# Mach_dieu_khien_dong_co_dc.net
KiCad netlist of a schematic drawn in Altium Designer
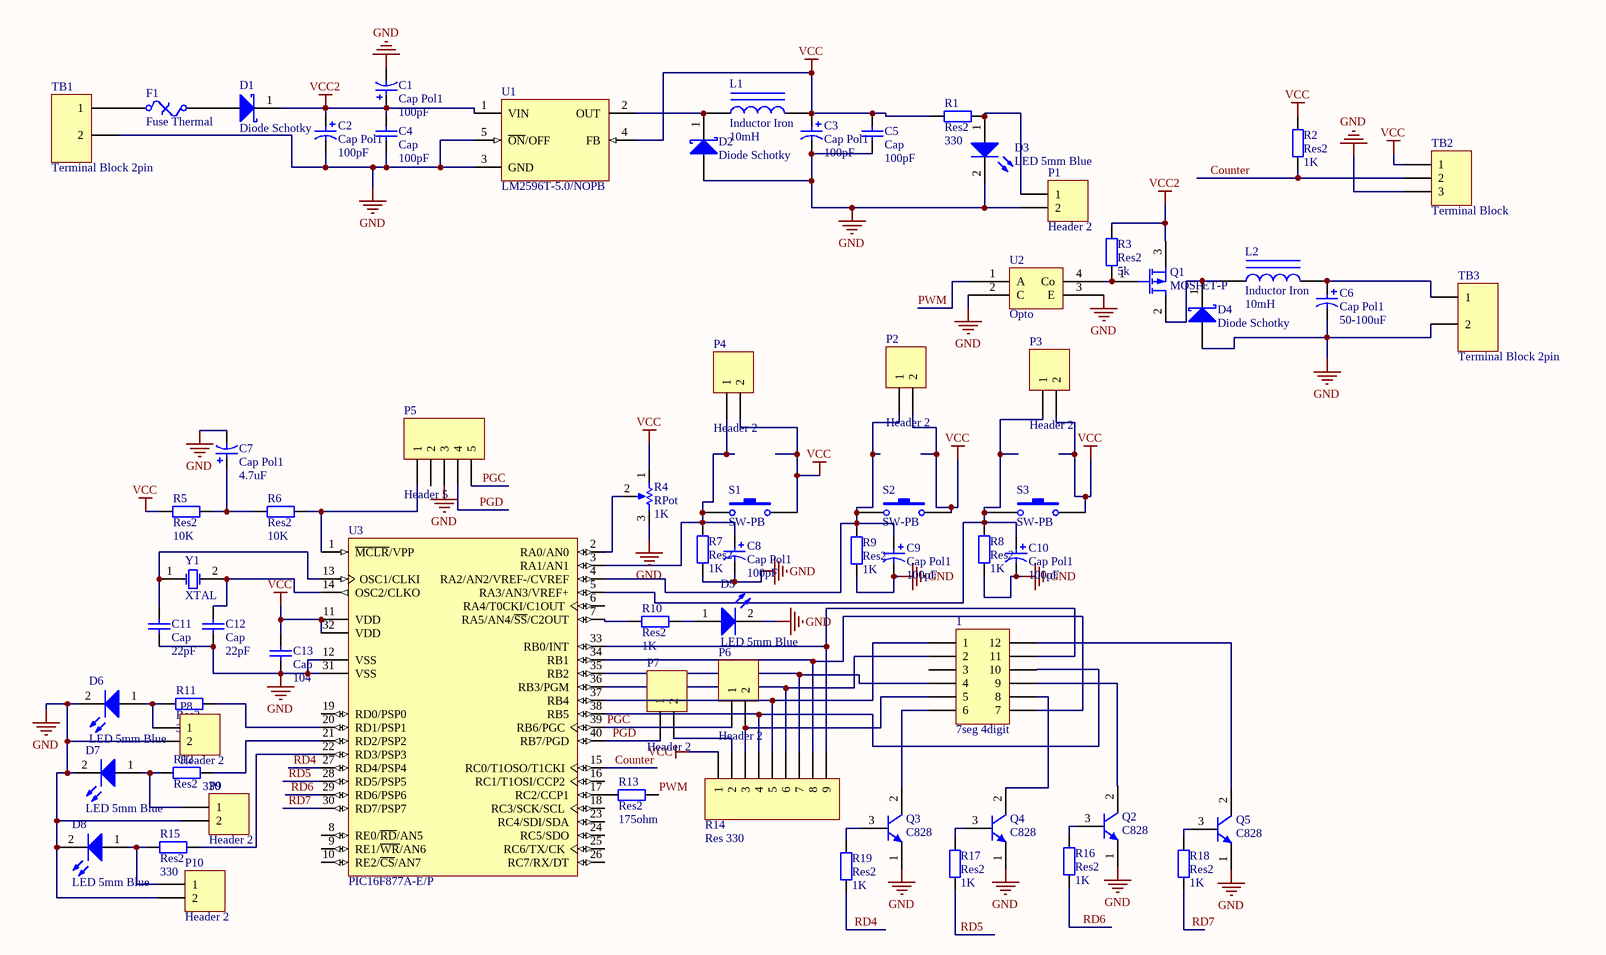
[diagram p0: Mach dieu khien dong co dc.SchDoc]

(export (version "E")
  (design (tool "Eeschema 10.0.6"))
  (components
    (comp (ref "1")
      (value "7seg 4digit")
      (footprint "LEDDIP-12/QUAD")
      (description "Header, 6-Pin, Dual row")
      (fields (field (name "PUBLISHER") "Altium Limited"))
      (libsource (lib "Manh") (part "7seg 4digit"))
    )
    (comp (ref "C1")
      (value "Cap Pol1")
      (footprint "Manh:CAPPR2-5x7")
      (description "Polarized Capacitor (Radial)")
      (fields (field (name "ALTIUM_VALUE") "100pF") (field (name "PUBLISHER") "Altium Limited"))
      (libsource (lib "Manh") (part "Cap Pol1"))
    )
    (comp (ref "C2")
      (value "Cap Pol1")
      (footprint "CAPPR2.5-6.3x5/H.9")
      (description "Polarized Capacitor (Radial)")
      (fields (field (name "ALTIUM_VALUE") "100pF") (field (name "PUBLISHER") "Altium Limited"))
      (libsource (lib "Manh") (part "Cap Pol1"))
    )
    (comp (ref "C3")
      (value "Cap Pol1")
      (footprint "CAPPR2.5-6.3x5/H.9")
      (description "Polarized Capacitor (Radial)")
      (fields (field (name "ALTIUM_VALUE") "100pF") (field (name "PUBLISHER") "Altium Limited"))
      (libsource (lib "Manh") (part "Cap Pol1"))
    )
    (comp (ref "C4")
      (value "Cap")
      (footprint "CAPNTO3.18-4.83x2.67")
      (description "Capacitor")
      (fields (field (name "ALTIUM_VALUE") "100pF") (field (name "PUBLISHER") "Altium Limited"))
      (libsource (lib "Manh") (part "Cap"))
    )
    (comp (ref "C5")
      (value "Cap")
      (footprint "CAPNTO3.18-4.83x2.67")
      (description "Capacitor")
      (fields (field (name "ALTIUM_VALUE") "100pF") (field (name "PUBLISHER") "Altium Limited"))
      (libsource (lib "Manh") (part "Cap"))
    )
    (comp (ref "C6")
      (value "Cap Pol1")
      (footprint "CAPPR2.5-6.3x5/H.9")
      (description "Polarized Capacitor (Radial)")
      (fields (field (name "ALTIUM_VALUE") "50-100uF") (field (name "PUBLISHER") "Altium Limited"))
      (libsource (lib "Manh") (part "Cap Pol1"))
    )
    (comp (ref "C7")
      (value "Cap Pol1")
      (footprint "CAPPR2-5x7")
      (description "Polarized Capacitor (Radial)")
      (fields (field (name "ALTIUM_VALUE") "4.7uF") (field (name "PUBLISHER") "Altium Limited"))
      (libsource (lib "Manh") (part "Cap Pol1"))
    )
    (comp (ref "C8")
      (value "Cap Pol1")
      (footprint "Manh:CAPPR2-5x7")
      (description "Polarized Capacitor (Radial)")
      (fields (field (name "ALTIUM_VALUE") "100pF") (field (name "PUBLISHER") "Altium Limited"))
      (libsource (lib "Manh") (part "Cap Pol1"))
    )
    (comp (ref "C9")
      (value "Cap Pol1")
      (footprint "Manh:CAPPR2-5x7")
      (description "Polarized Capacitor (Radial)")
      (fields (field (name "ALTIUM_VALUE") "100pF") (field (name "PUBLISHER") "Altium Limited"))
      (libsource (lib "Manh") (part "Cap Pol1"))
    )
    (comp (ref "C10")
      (value "Cap Pol1")
      (footprint "Manh:CAPPR2-5x7")
      (description "Polarized Capacitor (Radial)")
      (fields (field (name "ALTIUM_VALUE") "100pF") (field (name "PUBLISHER") "Altium Limited"))
      (libsource (lib "Manh") (part "Cap Pol1"))
    )
    (comp (ref "C11")
      (value "Cap")
      (footprint "CAPNTO3.18-4.83x2.67")
      (description "Capacitor")
      (fields (field (name "ALTIUM_VALUE") "22pF") (field (name "PUBLISHER") "Altium Limited"))
      (libsource (lib "Manh") (part "Cap"))
    )
    (comp (ref "C12")
      (value "Cap")
      (footprint "CAPNTO3.18-4.83x2.67")
      (description "Capacitor")
      (fields (field (name "ALTIUM_VALUE") "22pF") (field (name "PUBLISHER") "Altium Limited"))
      (libsource (lib "Manh") (part "Cap"))
    )
    (comp (ref "C13")
      (value "Cap")
      (footprint "CAPNTO3.18-4.83x2.67")
      (description "Capacitor")
      (fields (field (name "ALTIUM_VALUE") "104") (field (name "PUBLISHER") "Altium Limited"))
      (libsource (lib "Manh") (part "Cap"))
    )
    (comp (ref "D1")
      (value "Diode Schotky")
      (footprint "DO-201AD")
      (description "Schottky Rectifier")
      (fields (field (name "PUBLISHER") "Altium Limited"))
      (libsource (lib "Manh") (part "Diode Schotky"))
    )
    (comp (ref "D2")
      (value "Diode Schotky")
      (footprint "DO-41")
      (description "Schottky Rectifier")
      (fields (field (name "PUBLISHER") "Altium Limited"))
      (libsource (lib "Manh") (part "Diode Schotky"))
    )
    (comp (ref "D3")
      (value "LED 5mm Blue")
      (footprint "LED 5mm Blue")
      (description "Typical INFRARED GaAs LED")
      (fields (field (name "PUBLISHER") "Altium Limited"))
      (libsource (lib "Manh") (part "LED 5mm Blue"))
    )
    (comp (ref "D4")
      (value "Diode Schotky")
      (footprint "DO-41")
      (description "Schottky Rectifier")
      (fields (field (name "PUBLISHER") "Altium Limited"))
      (libsource (lib "Manh") (part "Diode Schotky"))
    )
    (comp (ref "D5")
      (value "LED 5mm Blue")
      (footprint "LED 5mm Blue")
      (description "Typical INFRARED GaAs LED")
      (fields (field (name "PUBLISHER") "Altium Limited"))
      (libsource (lib "Manh") (part "LED 5mm Blue"))
    )
    (comp (ref "D6")
      (value "LED 5mm Blue")
      (footprint "LED 5mm Blue")
      (description "Typical INFRARED GaAs LED")
      (fields (field (name "PUBLISHER") "Altium Limited"))
      (libsource (lib "Manh") (part "LED 5mm Blue"))
    )
    (comp (ref "D7")
      (value "LED 5mm Blue")
      (footprint "LED 5mm Blue")
      (description "Typical INFRARED GaAs LED")
      (fields (field (name "PUBLISHER") "Altium Limited"))
      (libsource (lib "Manh") (part "LED 5mm Blue"))
    )
    (comp (ref "D8")
      (value "LED 5mm Blue")
      (footprint "LED 5mm Blue")
      (description "Typical INFRARED GaAs LED")
      (fields (field (name "PUBLISHER") "Altium Limited"))
      (libsource (lib "Manh") (part "LED 5mm Blue"))
    )
    (comp (ref "F1")
      (value "Fuse Thermal")
      (footprint "PIN-W2/E2.8 -Manh")
      (description "Thermal Fuse")
      (fields (field (name "PUBLISHER") "Altium Limited"))
      (libsource (lib "Manh") (part "Fuse Thermal"))
    )
    (comp (ref "L1")
      (value "Inductor Iron")
      (footprint "Inductor power")
      (description "Magnetic-Core Inductor")
      (fields (field (name "ALTIUM_VALUE") "10mH") (field (name "PUBLISHER") "Altium Limited"))
      (libsource (lib "Manh") (part "Inductor Iron"))
    )
    (comp (ref "L2")
      (value "Inductor Iron")
      (footprint "Inductor power")
      (description "Magnetic-Core Inductor")
      (fields (field (name "ALTIUM_VALUE") "10mH") (field (name "PUBLISHER") "Altium Limited"))
      (libsource (lib "Manh") (part "Inductor Iron"))
    )
    (comp (ref "P1")
      (value "Header 2")
      (footprint "HDR1X2")
      (description "Header, 2-Pin")
      (fields (field (name "PUBLISHER") "Altium Limited"))
      (libsource (lib "") (part "Header 2_1"))
    )
    (comp (ref "P2")
      (value "Header 2")
      (footprint "HDR1X2")
      (description "Header, 2-Pin")
      (fields (field (name "PUBLISHER") "Altium Limited"))
      (libsource (lib "Manh") (part "Header 2"))
    )
    (comp (ref "P3")
      (value "Header 2")
      (footprint "HDR1X2")
      (description "Header, 2-Pin")
      (fields (field (name "PUBLISHER") "Altium Limited"))
      (libsource (lib "Manh") (part "Header 2"))
    )
    (comp (ref "P4")
      (value "Header 2")
      (footprint "HDR1X2")
      (description "Header, 2-Pin")
      (fields (field (name "PUBLISHER") "Altium Limited"))
      (libsource (lib "Manh") (part "Header 2"))
    )
    (comp (ref "P5")
      (value "Header 5")
      (footprint "HDR1X5")
      (description "Header, 5-Pin")
      (fields (field (name "PUBLISHER") "Altium Limited"))
      (libsource (lib "Manh") (part "Header 5"))
    )
    (comp (ref "P6")
      (value "Header 2")
      (footprint "HDR1X2")
      (description "Header, 2-Pin")
      (fields (field (name "PUBLISHER") "Altium Limited"))
      (libsource (lib "Manh") (part "Header 2"))
    )
    (comp (ref "P7")
      (value "Header 2")
      (footprint "HDR1X2")
      (description "Header, 2-Pin")
      (fields (field (name "PUBLISHER") "Altium Limited"))
      (libsource (lib "Manh") (part "Header 2"))
    )
    (comp (ref "P8")
      (value "Header 2")
      (footprint "HDR1X2")
      (description "Header, 2-Pin")
      (fields (field (name "PUBLISHER") "Altium Limited"))
      (libsource (lib "") (part "Header 2_1"))
    )
    (comp (ref "P9")
      (value "Header 2")
      (footprint "HDR1X2")
      (description "Header, 2-Pin")
      (fields (field (name "PUBLISHER") "Altium Limited"))
      (libsource (lib "") (part "Header 2_1"))
    )
    (comp (ref "P10")
      (value "Header 2")
      (footprint "HDR1X2")
      (description "Header, 2-Pin")
      (fields (field (name "PUBLISHER") "Altium Limited"))
      (libsource (lib "") (part "Header 2_1"))
    )
    (comp (ref "Q1")
      (value "MOSFET-P")
      (footprint "TO 220")
      (description "P-Channel MOSFET")
      (fields (field (name "PUBLISHER") "Altium Limited"))
      (libsource (lib "Manh") (part "MOSFET-P"))
    )
    (comp (ref "Q2")
      (value "C828")
      (footprint "TO-92-manh")
      (description "NPN General Purpose Amplifier")
      (fields (field (name "PUBLISHER") "Altium Limited"))
      (libsource (lib "Manh") (part "C828"))
    )
    (comp (ref "Q3")
      (value "C828")
      (footprint "TO-92-manh")
      (description "NPN General Purpose Amplifier")
      (fields (field (name "PUBLISHER") "Altium Limited"))
      (libsource (lib "Manh") (part "C828"))
    )
    (comp (ref "Q4")
      (value "C828")
      (footprint "TO-92-manh")
      (description "NPN General Purpose Amplifier")
      (fields (field (name "PUBLISHER") "Altium Limited"))
      (libsource (lib "Manh") (part "C828"))
    )
    (comp (ref "Q5")
      (value "C828")
      (footprint "TO-92-manh")
      (description "NPN General Purpose Amplifier")
      (fields (field (name "PUBLISHER") "Altium Limited"))
      (libsource (lib "Manh") (part "C828"))
    )
    (comp (ref "R1")
      (value "Res2")
      (footprint "AXIAL-0.4")
      (description "Resistor")
      (fields (field (name "ALTIUM_VALUE") "330") (field (name "PUBLISHER") "Altium Limited"))
      (libsource (lib "Manh") (part "Res2"))
    )
    (comp (ref "R2")
      (value "Res2")
      (footprint "AXIAL-0.4")
      (description "Resistor")
      (fields (field (name "ALTIUM_VALUE") "1K") (field (name "PUBLISHER") "Altium Limited"))
      (libsource (lib "") (part "Res2_2"))
    )
    (comp (ref "R3")
      (value "Res2")
      (footprint "AXIAL-0.4")
      (description "Resistor")
      (fields (field (name "ALTIUM_VALUE") "5k") (field (name "PUBLISHER") "Altium Limited"))
      (libsource (lib "") (part "Res2_1"))
    )
    (comp (ref "R4")
      (value "RPot")
      (footprint "Variable Resistor")
      (description "Potentiometer")
      (fields (field (name "ALTIUM_VALUE") "1K") (field (name "PUBLISHER") "Altium Limited"))
      (libsource (lib "Manh") (part "RPot"))
    )
    (comp (ref "R5")
      (value "Res2")
      (footprint "AXIAL-0.4")
      (description "Resistor")
      (fields (field (name "ALTIUM_VALUE") "10K") (field (name "PUBLISHER") "Altium Limited"))
      (libsource (lib "Manh") (part "Res2"))
    )
    (comp (ref "R6")
      (value "Res2")
      (footprint "AXIAL-0.4")
      (description "Resistor")
      (fields (field (name "ALTIUM_VALUE") "10K") (field (name "PUBLISHER") "Altium Limited"))
      (libsource (lib "Manh") (part "Res2"))
    )
    (comp (ref "R7")
      (value "Res2")
      (footprint "AXIAL-0.4")
      (description "Resistor")
      (fields (field (name "ALTIUM_VALUE") "1K") (field (name "PUBLISHER") "Altium Limited"))
      (libsource (lib "") (part "Res2_1"))
    )
    (comp (ref "R8")
      (value "Res2")
      (footprint "AXIAL-0.4")
      (description "Resistor")
      (fields (field (name "ALTIUM_VALUE") "1K") (field (name "PUBLISHER") "Altium Limited"))
      (libsource (lib "") (part "Res2_1"))
    )
    (comp (ref "R9")
      (value "Res2")
      (footprint "AXIAL-0.4")
      (description "Resistor")
      (fields (field (name "ALTIUM_VALUE") "1K") (field (name "PUBLISHER") "Altium Limited"))
      (libsource (lib "") (part "Res2_1"))
    )
    (comp (ref "R10")
      (value "Res2")
      (footprint "AXIAL-0.4")
      (description "Resistor")
      (fields (field (name "ALTIUM_VALUE") "1K") (field (name "PUBLISHER") "Altium Limited"))
      (libsource (lib "Manh") (part "Res2"))
    )
    (comp (ref "R11")
      (value "Res2")
      (footprint "AXIAL-0.4")
      (description "Resistor")
      (fields (field (name "ALTIUM_VALUE") "330") (field (name "PUBLISHER") "Altium Limited"))
      (libsource (lib "Manh") (part "Res2"))
    )
    (comp (ref "R12")
      (value "Res2")
      (footprint "AXIAL-0.4")
      (description "Resistor")
      (fields (field (name "ALTIUM_VALUE") "330") (field (name "PUBLISHER") "Altium Limited"))
      (libsource (lib "Manh") (part "Res2"))
    )
    (comp (ref "R13")
      (value "Res2")
      (footprint "AXIAL-0.4")
      (description "Resistor")
      (fields (field (name "ALTIUM_VALUE") "175ohm") (field (name "PUBLISHER") "Altium Limited"))
      (libsource (lib "") (part "Res2_3"))
    )
    (comp (ref "R14")
      (value "Res 330")
      (footprint "Res array 8")
      (description "Header, 9-Pin")
      (fields (field (name "PUBLISHER") "Altium Limited"))
      (libsource (lib "Manh") (part "Res array 8"))
    )
    (comp (ref "R15")
      (value "Res2")
      (footprint "AXIAL-0.4")
      (description "Resistor")
      (fields (field (name "ALTIUM_VALUE") "330") (field (name "PUBLISHER") "Altium Limited"))
      (libsource (lib "Manh") (part "Res2"))
    )
    (comp (ref "R16")
      (value "Res2")
      (footprint "AXIAL-0.4")
      (description "Resistor")
      (fields (field (name "ALTIUM_VALUE") "1K") (field (name "PUBLISHER") "Altium Limited"))
      (libsource (lib "") (part "Res2_1"))
    )
    (comp (ref "R17")
      (value "Res2")
      (footprint "AXIAL-0.4")
      (description "Resistor")
      (fields (field (name "ALTIUM_VALUE") "1K") (field (name "PUBLISHER") "Altium Limited"))
      (libsource (lib "") (part "Res2_1"))
    )
    (comp (ref "R18")
      (value "Res2")
      (footprint "AXIAL-0.4")
      (description "Resistor")
      (fields (field (name "ALTIUM_VALUE") "1K") (field (name "PUBLISHER") "Altium Limited"))
      (libsource (lib "") (part "Res2_1"))
    )
    (comp (ref "R19")
      (value "Res2")
      (footprint "AXIAL-0.4")
      (description "Resistor")
      (fields (field (name "ALTIUM_VALUE") "1K") (field (name "PUBLISHER") "Altium Limited"))
      (libsource (lib "") (part "Res2_1"))
    )
    (comp (ref "S1")
      (value "SW-PB")
      (footprint "Button DIP4")
      (description "Switch")
      (fields (field (name "PUBLISHER") "Altium Limited"))
      (libsource (lib "Manh") (part "SW-PB"))
    )
    (comp (ref "S2")
      (value "SW-PB")
      (footprint "Button DIP4")
      (description "Switch")
      (fields (field (name "PUBLISHER") "Altium Limited"))
      (libsource (lib "Manh") (part "SW-PB"))
    )
    (comp (ref "S3")
      (value "SW-PB")
      (footprint "Button DIP4")
      (description "Switch")
      (fields (field (name "PUBLISHER") "Altium Limited"))
      (libsource (lib "Manh") (part "SW-PB"))
    )
    (comp (ref "TB1")
      (value "Terminal Block 2pin")
      (footprint "Screw Terminal Block 2pin 5mm")
      (fields (field (name "PUBLISHER") "Altium Limited"))
      (libsource (lib "") (part "Terminal Block 2pin_1"))
    )
    (comp (ref "TB2")
      (value "Terminal Block")
      (footprint "Screw Terminal Block 3pin 5mm")
      (description "Terminal Block 3pin")
      (fields (field (name "PUBLISHER") "Altium Limited"))
      (libsource (lib "Manh") (part "Terminal Block 3pin"))
    )
    (comp (ref "TB3")
      (value "Terminal Block 2pin")
      (footprint "Screw Terminal Block 2pin 5mm")
      (fields (field (name "PUBLISHER") "Altium Limited"))
      (libsource (lib "Manh") (part "Terminal Block 2pin"))
    )
    (comp (ref "U1")
      (value "LM2596T-5.0/NOPB")
      (footprint "T05D")
      (description "SIMPLE SWITCHER® Power Converter 150 KHz 3A Step-Down Voltage Regulator, 5-pin TO-220, Pb-Free")
      (fields
        (field (name "MANUFACTURER") "National Semiconductor")
        (field (name "PUBLISHER") "Altium Limited")
      )
      (libsource (lib "Manh") (part "LM2596T-5.0/NOPB"))
    )
    (comp (ref "U2") (value "Opto") (footprint "DIP-6 -v2") (libsource (lib "Manh") (part "Opto 1")))
    (comp (ref "U3")
      (value "PIC16F877A-E/P")
      (footprint "Manh:PDIP600-40")
      (fields (field (name "PUBLISHER") "Altium Limited"))
      (libsource (lib "Manh") (part "PIC16F877A-E/P"))
    )
    (comp (ref "Y1")
      (value "XTAL")
      (footprint "R38")
      (description "Crystal Oscillator")
      (fields (field (name "PUBLISHER") "Altium Limited"))
      (libsource (lib "Manh") (part "XTAL"))
    )
  )
  (nets
    (net (code "1") (name "/Counter") (class "Default")
      (node (ref "R2") (pin "2") (pinfunction "2_2") (pintype "passive"))
      (node (ref "TB2") (pin "2") (pinfunction "2_2") (pintype "passive"))
      (node (ref "U3") (pin "15") (pinfunction "RC0/T1OSO/T1CKI_15") (pintype "bidirectional"))
    )
    (net (code "2") (name "/PGC") (class "Default")
      (node (ref "P5") (pin "5") (pinfunction "5_5") (pintype "passive"))
      (node (ref "P6") (pin "1") (pinfunction "1_1") (pintype "passive"))
      (node (ref "U3") (pin "39") (pinfunction "RB6/PGC_39") (pintype "bidirectional"))
    )
    (net (code "3") (name "/PGD") (class "Default")
      (node (ref "P5") (pin "4") (pinfunction "4_4") (pintype "passive"))
      (node (ref "P7") (pin "1") (pinfunction "1_1") (pintype "passive"))
      (node (ref "U3") (pin "40") (pinfunction "RB7/PGD_40") (pintype "bidirectional"))
    )
    (net (code "4") (name "/PWM") (class "Default")
      (node (ref "R13") (pin "1") (pinfunction "1_1") (pintype "passive"))
      (node (ref "U2") (pin "1") (pinfunction "A_1") (pintype "passive"))
    )
    (net (code "5") (name "/RD4") (class "Default")
      (node (ref "R19") (pin "1") (pinfunction "1_1") (pintype "passive"))
      (node (ref "U3") (pin "27") (pinfunction "RD4/PSP4_27") (pintype "bidirectional"))
    )
    (net (code "6") (name "/RD5") (class "Default")
      (node (ref "R17") (pin "1") (pinfunction "1_1") (pintype "passive"))
      (node (ref "U3") (pin "28") (pinfunction "RD5/PSP5_28") (pintype "bidirectional"))
    )
    (net (code "7") (name "/RD6") (class "Default")
      (node (ref "R16") (pin "1") (pinfunction "1_1") (pintype "passive"))
      (node (ref "U3") (pin "29") (pinfunction "RD6/PSP6_29") (pintype "bidirectional"))
    )
    (net (code "8") (name "/RD7") (class "Default")
      (node (ref "R18") (pin "1") (pinfunction "1_1") (pintype "passive"))
      (node (ref "U3") (pin "30") (pinfunction "RD7/PSP7_30") (pintype "bidirectional"))
    )
    (net (code "9") (name "GND") (class "Default")
      (node (ref "C1") (pin "2") (pinfunction "2_2") (pintype "passive"))
      (node (ref "C10") (pin "2") (pinfunction "2_2") (pintype "passive"))
      (node (ref "C11") (pin "1") (pinfunction "1_1") (pintype "passive"))
      (node (ref "C12") (pin "1") (pinfunction "1_1") (pintype "passive"))
      (node (ref "C13") (pin "1") (pinfunction "1_1") (pintype "passive"))
      (node (ref "C2") (pin "2") (pinfunction "2_2") (pintype "passive"))
      (node (ref "C3") (pin "2") (pinfunction "2_2") (pintype "passive"))
      (node (ref "C4") (pin "1") (pinfunction "1_1") (pintype "passive"))
      (node (ref "C5") (pin "1") (pinfunction "1_1") (pintype "passive"))
      (node (ref "C6") (pin "2") (pinfunction "2_2") (pintype "passive"))
      (node (ref "C7") (pin "2") (pinfunction "2_2") (pintype "passive"))
      (node (ref "C8") (pin "2") (pinfunction "2_2") (pintype "passive"))
      (node (ref "C9") (pin "2") (pinfunction "2_2") (pintype "passive"))
      (node (ref "D2") (pin "2") (pinfunction "A_2") (pintype "passive"))
      (node (ref "D3") (pin "2") (pinfunction "K_2") (pintype "passive"))
      (node (ref "D4") (pin "2") (pinfunction "A_2") (pintype "passive"))
      (node (ref "D5") (pin "2") (pinfunction "K_2") (pintype "passive"))
      (node (ref "D6") (pin "2") (pinfunction "K_2") (pintype "passive"))
      (node (ref "D7") (pin "2") (pinfunction "K_2") (pintype "passive"))
      (node (ref "D8") (pin "2") (pinfunction "K_2") (pintype "passive"))
      (node (ref "P1") (pin "2") (pinfunction "2_2") (pintype "passive"))
      (node (ref "P10") (pin "2") (pinfunction "2_2") (pintype "passive"))
      (node (ref "P5") (pin "3") (pinfunction "3_3") (pintype "passive"))
      (node (ref "P8") (pin "2") (pinfunction "2_2") (pintype "passive"))
      (node (ref "P9") (pin "2") (pinfunction "2_2") (pintype "passive"))
      (node (ref "Q2") (pin "1") (pinfunction "E_1") (pintype "passive"))
      (node (ref "Q3") (pin "1") (pinfunction "E_1") (pintype "passive"))
      (node (ref "Q4") (pin "1") (pinfunction "E_1") (pintype "passive"))
      (node (ref "Q5") (pin "1") (pinfunction "E_1") (pintype "passive"))
      (node (ref "R4") (pin "3") (pinfunction "BOT_3") (pintype "passive"))
      (node (ref "R7") (pin "1") (pinfunction "1_1") (pintype "passive"))
      (node (ref "R8") (pin "1") (pinfunction "1_1") (pintype "passive"))
      (node (ref "R9") (pin "1") (pinfunction "1_1") (pintype "passive"))
      (node (ref "TB1") (pin "2") (pinfunction "2_2") (pintype "passive"))
      (node (ref "TB2") (pin "3") (pinfunction "3_3") (pintype "passive"))
      (node (ref "TB3") (pin "2") (pinfunction "2_2") (pintype "passive"))
      (node (ref "U1") (pin "3") (pinfunction "GND_3") (pintype "power_in"))
      (node (ref "U1") (pin "5") (pinfunction "~{ON}/OFF_5") (pintype "input"))
      (node (ref "U2") (pin "2") (pinfunction "C_2") (pintype "passive"))
      (node (ref "U2") (pin "3") (pinfunction "E_3") (pintype "passive"))
      (node (ref "U3") (pin "12") (pinfunction "VSS_12") (pintype "power_in"))
      (node (ref "U3") (pin "31") (pinfunction "VSS_31") (pintype "power_in"))
    )
    (net (code "10") (name "Net-(1-Pad5)") (class "Default")
      (node (ref "1") (pin "5") (pinfunction "5_5") (pintype "passive"))
      (node (ref "P6") (pin "2") (pinfunction "2_2") (pintype "passive"))
      (node (ref "R14") (pin "3") (pinfunction "3_3") (pintype "passive"))
    )
    (net (code "11") (name "Net-(C6-Pad1)") (class "Default")
      (node (ref "C6") (pin "1") (pinfunction "1_1") (pintype "passive"))
      (node (ref "L2") (pin "2") (pinfunction "2_2") (pintype "passive"))
      (node (ref "TB3") (pin "1") (pinfunction "1_1") (pintype "passive"))
    )
    (net (code "12") (name "Net-(C7-Pad1)") (class "Default")
      (node (ref "C7") (pin "1") (pinfunction "1_1") (pintype "passive"))
      (node (ref "R5") (pin "2") (pinfunction "2_2") (pintype "passive"))
      (node (ref "R6") (pin "1") (pinfunction "1_1") (pintype "passive"))
    )
    (net (code "13") (name "Net-(D1-A)") (class "Default")
      (node (ref "D1") (pin "2") (pinfunction "A_2") (pintype "passive"))
      (node (ref "F1") (pin "2") (pinfunction "2_2") (pintype "passive"))
    )
    (net (code "14") (name "Net-(D2-K)") (class "Default")
      (node (ref "D2") (pin "1") (pinfunction "K_1") (pintype "passive"))
      (node (ref "L1") (pin "1") (pinfunction "1_1") (pintype "passive"))
      (node (ref "U1") (pin "2") (pinfunction "OUT_2") (pintype "power_in"))
    )
    (net (code "15") (name "Net-(D3-A)") (class "Default")
      (node (ref "D3") (pin "1") (pinfunction "A_1") (pintype "passive"))
      (node (ref "P1") (pin "1") (pinfunction "1_1") (pintype "passive"))
      (node (ref "R1") (pin "2") (pinfunction "2_2") (pintype "passive"))
    )
    (net (code "16") (name "Net-(D4-K)") (class "Default")
      (node (ref "D4") (pin "1") (pinfunction "K_1") (pintype "passive"))
      (node (ref "L2") (pin "1") (pinfunction "1_1") (pintype "passive"))
      (node (ref "Q1") (pin "2") (pinfunction "D_2") (pintype "passive"))
    )
    (net (code "17") (name "Net-(D5-A)") (class "Default")
      (node (ref "D5") (pin "1") (pinfunction "A_1") (pintype "passive"))
      (node (ref "R10") (pin "2") (pinfunction "2_2") (pintype "passive"))
    )
    (net (code "18") (name "Net-(D6-A)") (class "Default")
      (node (ref "D6") (pin "1") (pinfunction "A_1") (pintype "passive"))
      (node (ref "P8") (pin "1") (pinfunction "1_1") (pintype "passive"))
      (node (ref "R11") (pin "1") (pinfunction "1_1") (pintype "passive"))
    )
    (net (code "19") (name "Net-(D7-A)") (class "Default")
      (node (ref "D7") (pin "1") (pinfunction "A_1") (pintype "passive"))
      (node (ref "P9") (pin "1") (pinfunction "1_1") (pintype "passive"))
      (node (ref "R12") (pin "1") (pinfunction "1_1") (pintype "passive"))
    )
    (net (code "20") (name "Net-(D8-A)") (class "Default")
      (node (ref "D8") (pin "1") (pinfunction "A_1") (pintype "passive"))
      (node (ref "P10") (pin "1") (pinfunction "1_1") (pintype "passive"))
      (node (ref "R15") (pin "1") (pinfunction "1_1") (pintype "passive"))
    )
    (net (code "21") (name "Net-(F1-Pad1)") (class "Default")
      (node (ref "F1") (pin "1") (pinfunction "1_1") (pintype "passive"))
      (node (ref "TB1") (pin "1") (pinfunction "1_1") (pintype "passive"))
    )
    (net (code "22") (name "Net-(P7-Pad2)") (class "Default")
      (node (ref "P7") (pin "2") (pinfunction "2_2") (pintype "passive"))
      (node (ref "R14") (pin "2") (pinfunction "2_2") (pintype "passive"))
    )
    (net (code "23") (name "Net-(Q1-G)") (class "Default")
      (node (ref "Q1") (pin "1") (pinfunction "G_1") (pintype "passive"))
      (node (ref "R3") (pin "1") (pinfunction "1_1") (pintype "passive"))
      (node (ref "U2") (pin "4") (pinfunction "Co_4") (pintype "passive"))
    )
    (net (code "24") (name "Net-(Q2-B)") (class "Default")
      (node (ref "Q2") (pin "3") (pinfunction "B_3") (pintype "passive"))
      (node (ref "R16") (pin "2") (pinfunction "2_2") (pintype "passive"))
    )
    (net (code "25") (name "Net-(Q2-C)") (class "Default")
      (node (ref "1") (pin "9") (pinfunction "9_9") (pintype "passive"))
      (node (ref "Q2") (pin "2") (pinfunction "C_2") (pintype "passive"))
    )
    (net (code "26") (name "Net-(Q3-B)") (class "Default")
      (node (ref "Q3") (pin "3") (pinfunction "B_3") (pintype "passive"))
      (node (ref "R19") (pin "2") (pinfunction "2_2") (pintype "passive"))
    )
    (net (code "27") (name "Net-(Q3-C)") (class "Default")
      (node (ref "1") (pin "6") (pinfunction "6_6") (pintype "passive"))
      (node (ref "Q3") (pin "2") (pinfunction "C_2") (pintype "passive"))
    )
    (net (code "28") (name "Net-(Q4-B)") (class "Default")
      (node (ref "Q4") (pin "3") (pinfunction "B_3") (pintype "passive"))
      (node (ref "R17") (pin "2") (pinfunction "2_2") (pintype "passive"))
    )
    (net (code "29") (name "Net-(Q4-C)") (class "Default")
      (node (ref "1") (pin "8") (pinfunction "8_8") (pintype "passive"))
      (node (ref "Q4") (pin "2") (pinfunction "C_2") (pintype "passive"))
    )
    (net (code "30") (name "Net-(Q5-B)") (class "Default")
      (node (ref "Q5") (pin "3") (pinfunction "B_3") (pintype "passive"))
      (node (ref "R18") (pin "2") (pinfunction "2_2") (pintype "passive"))
    )
    (net (code "31") (name "Net-(Q5-C)") (class "Default")
      (node (ref "1") (pin "12") (pinfunction "12_12") (pintype "passive"))
      (node (ref "Q5") (pin "2") (pinfunction "C_2") (pintype "passive"))
    )
    (net (code "32") (name "Net-(R4-TAP)") (class "Default")
      (node (ref "R4") (pin "2") (pinfunction "TAP_2") (pintype "passive"))
      (node (ref "U3") (pin "2") (pinfunction "RA0/AN0_2") (pintype "bidirectional"))
    )
    (net (code "33") (name "Net-(U3-OSC1{slash}CLKI)") (class "Default")
      (node (ref "C11") (pin "2") (pinfunction "2_2") (pintype "passive"))
      (node (ref "U3") (pin "13") (pinfunction "OSC1/CLKI_13") (pintype "input"))
      (node (ref "Y1") (pin "1") (pinfunction "OSC1_1") (pintype "passive"))
    )
    (net (code "34") (name "Net-(U3-OSC2{slash}CLKO)") (class "Default")
      (node (ref "C12") (pin "2") (pinfunction "2_2") (pintype "passive"))
      (node (ref "U3") (pin "14") (pinfunction "OSC2/CLKO_14") (pintype "output"))
      (node (ref "Y1") (pin "2") (pinfunction "OSC2_2") (pintype "passive"))
    )
    (net (code "35") (name "Net-(U3-RA1{slash}AN1)") (class "Default")
      (node (ref "C8") (pin "1") (pinfunction "1_1") (pintype "passive"))
      (node (ref "P4") (pin "1") (pinfunction "1_1") (pintype "passive"))
      (node (ref "R7") (pin "2") (pinfunction "2_2") (pintype "passive"))
      (node (ref "S1") (pin "1") (pinfunction "1_1") (pintype "passive"))
      (node (ref "U3") (pin "3") (pinfunction "RA1/AN1_3") (pintype "bidirectional"))
    )
    (net (code "36") (name "Net-(U3-RA2{slash}AN2{slash}VREF-{slash}CVREF)") (class "Default")
      (node (ref "C9") (pin "1") (pinfunction "1_1") (pintype "passive"))
      (node (ref "P2") (pin "1") (pinfunction "1_1") (pintype "passive"))
      (node (ref "R9") (pin "2") (pinfunction "2_2") (pintype "passive"))
      (node (ref "S2") (pin "1") (pinfunction "1_1") (pintype "passive"))
      (node (ref "U3") (pin "4") (pinfunction "RA2/AN2/VREF-/CVREF_4") (pintype "bidirectional"))
    )
    (net (code "37") (name "Net-(U3-RA3{slash}AN3{slash}VREF+)") (class "Default")
      (node (ref "C10") (pin "1") (pinfunction "1_1") (pintype "passive"))
      (node (ref "P3") (pin "1") (pinfunction "1_1") (pintype "passive"))
      (node (ref "R8") (pin "2") (pinfunction "2_2") (pintype "passive"))
      (node (ref "S3") (pin "1") (pinfunction "1_1") (pintype "passive"))
      (node (ref "U3") (pin "5") (pinfunction "RA3/AN3/VREF+_5") (pintype "bidirectional"))
    )
    (net (code "38") (name "Net-(U3-RA5{slash}AN4{slash}~{SS}{slash}C2OUT)") (class "Default")
      (node (ref "R10") (pin "1") (pinfunction "1_1") (pintype "passive"))
      (node (ref "U3") (pin "7") (pinfunction "RA5/AN4/~{SS}/C2OUT_7") (pintype "bidirectional"))
    )
    (net (code "39") (name "Net-(U3-RB0{slash}INT)") (class "Default")
      (node (ref "1") (pin "11") (pinfunction "11_11") (pintype "passive"))
      (node (ref "R14") (pin "9") (pinfunction "9_9") (pintype "passive"))
      (node (ref "U3") (pin "33") (pinfunction "RB0/INT_33") (pintype "bidirectional"))
    )
    (net (code "40") (name "Net-(U3-RB1)") (class "Default")
      (node (ref "1") (pin "7") (pinfunction "7_7") (pintype "passive"))
      (node (ref "R14") (pin "8") (pinfunction "8_8") (pintype "passive"))
      (node (ref "U3") (pin "34") (pinfunction "RB1_34") (pintype "bidirectional"))
    )
    (net (code "41") (name "Net-(U3-RB2)") (class "Default")
      (node (ref "1") (pin "4") (pinfunction "4_4") (pintype "passive"))
      (node (ref "R14") (pin "7") (pinfunction "7_7") (pintype "passive"))
      (node (ref "U3") (pin "35") (pinfunction "RB2_35") (pintype "bidirectional"))
    )
    (net (code "42") (name "Net-(U3-RB3{slash}PGM)") (class "Default")
      (node (ref "1") (pin "2") (pinfunction "2_2") (pintype "passive"))
      (node (ref "R14") (pin "6") (pinfunction "6_6") (pintype "passive"))
      (node (ref "U3") (pin "36") (pinfunction "RB3/PGM_36") (pintype "bidirectional"))
    )
    (net (code "43") (name "Net-(U3-RB4)") (class "Default")
      (node (ref "1") (pin "1") (pinfunction "1_1") (pintype "passive"))
      (node (ref "R14") (pin "5") (pinfunction "5_5") (pintype "passive"))
      (node (ref "U3") (pin "37") (pinfunction "RB4_37") (pintype "bidirectional"))
    )
    (net (code "44") (name "Net-(U3-RB5)") (class "Default")
      (node (ref "1") (pin "10") (pinfunction "10_10") (pintype "passive"))
      (node (ref "R14") (pin "4") (pinfunction "4_4") (pintype "passive"))
      (node (ref "U3") (pin "38") (pinfunction "RB5_38") (pintype "bidirectional"))
    )
    (net (code "45") (name "Net-(U3-RC2{slash}CCP1)") (class "Default")
      (node (ref "R13") (pin "2") (pinfunction "2_2") (pintype "passive"))
      (node (ref "U3") (pin "17") (pinfunction "RC2/CCP1_17") (pintype "bidirectional"))
    )
    (net (code "46") (name "Net-(U3-RD1{slash}PSP1)") (class "Default")
      (node (ref "R11") (pin "2") (pinfunction "2_2") (pintype "passive"))
      (node (ref "U3") (pin "20") (pinfunction "RD1/PSP1_20") (pintype "bidirectional"))
    )
    (net (code "47") (name "Net-(U3-RD2{slash}PSP2)") (class "Default")
      (node (ref "R12") (pin "2") (pinfunction "2_2") (pintype "passive"))
      (node (ref "U3") (pin "21") (pinfunction "RD2/PSP2_21") (pintype "bidirectional"))
    )
    (net (code "48") (name "Net-(U3-RD3{slash}PSP3)") (class "Default")
      (node (ref "R15") (pin "2") (pinfunction "2_2") (pintype "passive"))
      (node (ref "U3") (pin "22") (pinfunction "RD3/PSP3_22") (pintype "bidirectional"))
    )
    (net (code "49") (name "Net-(U3-~{MCLR}{slash}VPP)") (class "Default")
      (node (ref "P5") (pin "1") (pinfunction "1_1") (pintype "passive"))
      (node (ref "R6") (pin "2") (pinfunction "2_2") (pintype "passive"))
      (node (ref "U3") (pin "1") (pinfunction "~{MCLR}/VPP_1") (pintype "input"))
    )
    (net (code "50") (name "VCC") (class "Default")
      (node (ref "C13") (pin "2") (pinfunction "2_2") (pintype "passive"))
      (node (ref "C3") (pin "1") (pinfunction "1_1") (pintype "passive"))
      (node (ref "C5") (pin "2") (pinfunction "2_2") (pintype "passive"))
      (node (ref "L1") (pin "2") (pinfunction "2_2") (pintype "passive"))
      (node (ref "P2") (pin "2") (pinfunction "2_2") (pintype "passive"))
      (node (ref "P3") (pin "2") (pinfunction "2_2") (pintype "passive"))
      (node (ref "P4") (pin "2") (pinfunction "2_2") (pintype "passive"))
      (node (ref "R1") (pin "1") (pinfunction "1_1") (pintype "passive"))
      (node (ref "R14") (pin "1") (pinfunction "1_1") (pintype "passive"))
      (node (ref "R2") (pin "1") (pinfunction "1_1") (pintype "passive"))
      (node (ref "R4") (pin "1") (pinfunction "TOP_1") (pintype "passive"))
      (node (ref "R5") (pin "1") (pinfunction "1_1") (pintype "passive"))
      (node (ref "S1") (pin "2") (pinfunction "2_2") (pintype "passive"))
      (node (ref "S2") (pin "2") (pinfunction "2_2") (pintype "passive"))
      (node (ref "S3") (pin "2") (pinfunction "2_2") (pintype "passive"))
      (node (ref "TB2") (pin "1") (pinfunction "1_1") (pintype "passive"))
      (node (ref "U1") (pin "4") (pinfunction "FB_4") (pintype "input"))
      (node (ref "U3") (pin "11") (pinfunction "VDD_11") (pintype "power_in"))
      (node (ref "U3") (pin "32") (pinfunction "VDD_32") (pintype "power_in"))
    )
    (net (code "51") (name "VCC2") (class "Default")
      (node (ref "C1") (pin "1") (pinfunction "1_1") (pintype "passive"))
      (node (ref "C2") (pin "1") (pinfunction "1_1") (pintype "passive"))
      (node (ref "C4") (pin "2") (pinfunction "2_2") (pintype "passive"))
      (node (ref "D1") (pin "1") (pinfunction "K_1") (pintype "passive"))
      (node (ref "Q1") (pin "3") (pinfunction "S_3") (pintype "passive"))
      (node (ref "R3") (pin "2") (pinfunction "2_2") (pintype "passive"))
      (node (ref "U1") (pin "1") (pinfunction "VIN_1") (pintype "power_in"))
    )
    (net (code "52") (name "unconnected-(1-Pad3)") (class "Default")
      (node (ref "1") (pin "3") (pinfunction "3_3") (pintype "passive"))
    )
    (net (code "53") (name "unconnected-(P5-Pad2)") (class "Default")
      (node (ref "P5") (pin "2") (pinfunction "2_2") (pintype "passive"))
    )
    (net (code "54") (name "unconnected-(U3-RA4{slash}T0CKI{slash}C1OUT-Pad6)") (class "Default")
      (node (ref "U3") (pin "6") (pinfunction "RA4/T0CKI/C1OUT_6") (pintype "bidirectional"))
    )
    (net (code "55") (name "unconnected-(U3-RC1{slash}T1OSI{slash}CCP2-Pad16)") (class "Default")
      (node (ref "U3") (pin "16") (pinfunction "RC1/T1OSI/CCP2_16") (pintype "bidirectional"))
    )
    (net (code "56") (name "unconnected-(U3-RC3{slash}SCK{slash}SCL-Pad18)") (class "Default")
      (node (ref "U3") (pin "18") (pinfunction "RC3/SCK/SCL_18") (pintype "bidirectional"))
    )
    (net (code "57") (name "unconnected-(U3-RC4{slash}SDI{slash}SDA-Pad23)") (class "Default")
      (node (ref "U3") (pin "23") (pinfunction "RC4/SDI/SDA_23") (pintype "bidirectional"))
    )
    (net (code "58") (name "unconnected-(U3-RC5{slash}SDO-Pad24)") (class "Default")
      (node (ref "U3") (pin "24") (pinfunction "RC5/SDO_24") (pintype "bidirectional"))
    )
    (net (code "59") (name "unconnected-(U3-RC6{slash}TX{slash}CK-Pad25)") (class "Default")
      (node (ref "U3") (pin "25") (pinfunction "RC6/TX/CK_25") (pintype "bidirectional"))
    )
    (net (code "60") (name "unconnected-(U3-RC7{slash}RX{slash}DT-Pad26)") (class "Default")
      (node (ref "U3") (pin "26") (pinfunction "RC7/RX/DT_26") (pintype "bidirectional"))
    )
    (net (code "61") (name "unconnected-(U3-RD0{slash}PSP0-Pad19)") (class "Default")
      (node (ref "U3") (pin "19") (pinfunction "RD0/PSP0_19") (pintype "bidirectional"))
    )
    (net (code "62") (name "unconnected-(U3-RE0{slash}~{RD}{slash}AN5-Pad8)") (class "Default")
      (node (ref "U3") (pin "8") (pinfunction "RE0/~{RD}/AN5_8") (pintype "bidirectional"))
    )
    (net (code "63") (name "unconnected-(U3-RE1{slash}~{WR}{slash}AN6-Pad9)") (class "Default")
      (node (ref "U3") (pin "9") (pinfunction "RE1/~{WR}/AN6_9") (pintype "bidirectional"))
    )
    (net (code "64") (name "unconnected-(U3-RE2{slash}~{CS}{slash}AN7-Pad10)") (class "Default")
      (node (ref "U3") (pin "10") (pinfunction "RE2/~{CS}/AN7_10") (pintype "bidirectional"))
    )
  )
)
